# breakout.net
KiCad netlist of a schematic drawn in EAGLE
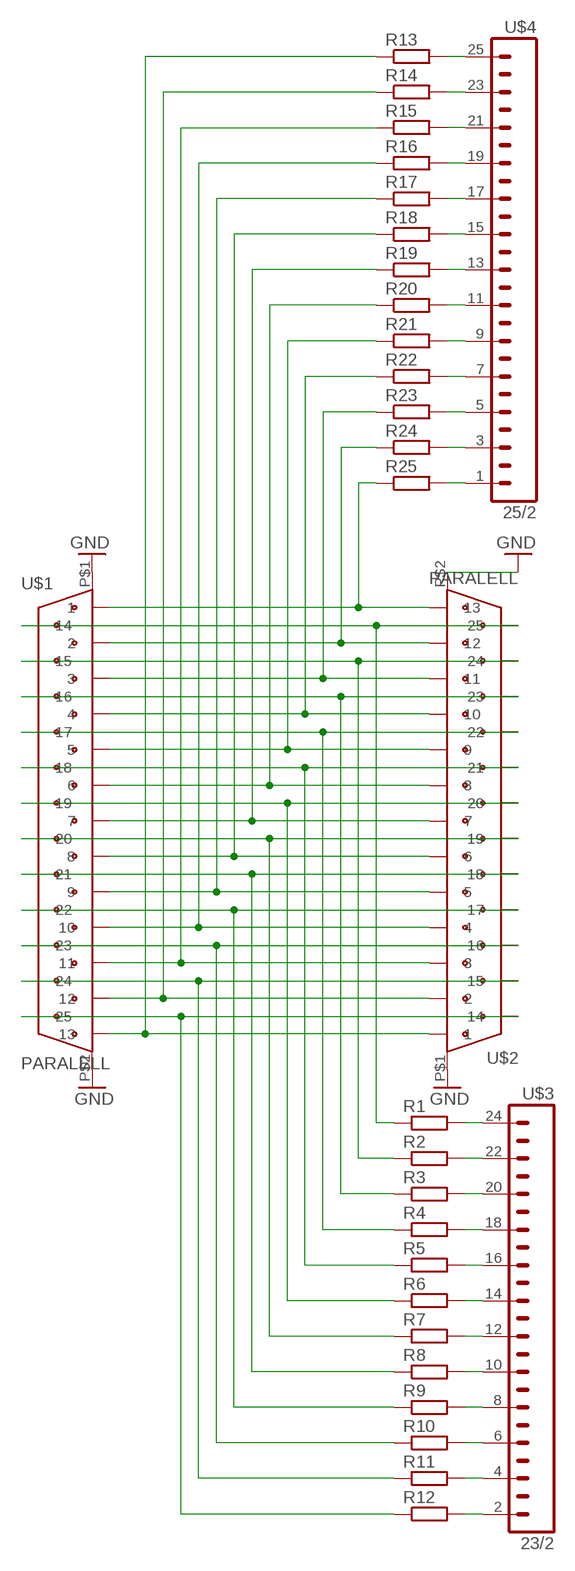
[diagram p0: schematic, sheet 1]

(export (version "E")
  (design (tool "Eeschema 10.0.6"))
  (components
    (comp (ref "R1")
      (value "R-EU_0204/7")
      (footprint "eagle-import:0204_7")
      (libsource (lib "eagle-import") (part "R-EU_0204/7"))
    )
    (comp (ref "R2")
      (value "R-EU_0204/7")
      (footprint "eagle-import:0204_7")
      (libsource (lib "eagle-import") (part "R-EU_0204/7"))
    )
    (comp (ref "R3")
      (value "R-EU_0204/7")
      (footprint "eagle-import:0204_7")
      (libsource (lib "eagle-import") (part "R-EU_0204/7"))
    )
    (comp (ref "R4")
      (value "R-EU_0204/7")
      (footprint "eagle-import:0204_7")
      (libsource (lib "eagle-import") (part "R-EU_0204/7"))
    )
    (comp (ref "R5")
      (value "R-EU_0204/7")
      (footprint "eagle-import:0204_7")
      (libsource (lib "eagle-import") (part "R-EU_0204/7"))
    )
    (comp (ref "R6")
      (value "R-EU_0204/7")
      (footprint "eagle-import:0204_7")
      (libsource (lib "eagle-import") (part "R-EU_0204/7"))
    )
    (comp (ref "R7")
      (value "R-EU_0204/7")
      (footprint "eagle-import:0204_7")
      (libsource (lib "eagle-import") (part "R-EU_0204/7"))
    )
    (comp (ref "R8")
      (value "R-EU_0204/7")
      (footprint "eagle-import:0204_7")
      (libsource (lib "eagle-import") (part "R-EU_0204/7"))
    )
    (comp (ref "R9")
      (value "R-EU_0204/7")
      (footprint "eagle-import:0204_7")
      (libsource (lib "eagle-import") (part "R-EU_0204/7"))
    )
    (comp (ref "R10")
      (value "R-EU_0204/7")
      (footprint "eagle-import:0204_7")
      (libsource (lib "eagle-import") (part "R-EU_0204/7"))
    )
    (comp (ref "R11")
      (value "R-EU_0204/7")
      (footprint "eagle-import:0204_7")
      (libsource (lib "eagle-import") (part "R-EU_0204/7"))
    )
    (comp (ref "R12")
      (value "R-EU_0204/7")
      (footprint "eagle-import:0204_7")
      (libsource (lib "eagle-import") (part "R-EU_0204/7"))
    )
    (comp (ref "R13")
      (value "R-EU_0204/7")
      (footprint "eagle-import:0204_7")
      (libsource (lib "eagle-import") (part "R-EU_0204/7"))
    )
    (comp (ref "R14")
      (value "R-EU_0204/7")
      (footprint "eagle-import:0204_7")
      (libsource (lib "eagle-import") (part "R-EU_0204/7"))
    )
    (comp (ref "R15")
      (value "R-EU_0204/7")
      (footprint "eagle-import:0204_7")
      (libsource (lib "eagle-import") (part "R-EU_0204/7"))
    )
    (comp (ref "R16")
      (value "R-EU_0204/7")
      (footprint "eagle-import:0204_7")
      (libsource (lib "eagle-import") (part "R-EU_0204/7"))
    )
    (comp (ref "R17")
      (value "R-EU_0204/7")
      (footprint "eagle-import:0204_7")
      (libsource (lib "eagle-import") (part "R-EU_0204/7"))
    )
    (comp (ref "R18")
      (value "R-EU_0204/7")
      (footprint "eagle-import:0204_7")
      (libsource (lib "eagle-import") (part "R-EU_0204/7"))
    )
    (comp (ref "R19")
      (value "R-EU_0204/7")
      (footprint "eagle-import:0204_7")
      (libsource (lib "eagle-import") (part "R-EU_0204/7"))
    )
    (comp (ref "R20")
      (value "R-EU_0204/7")
      (footprint "eagle-import:0204_7")
      (libsource (lib "eagle-import") (part "R-EU_0204/7"))
    )
    (comp (ref "R21")
      (value "R-EU_0204/7")
      (footprint "eagle-import:0204_7")
      (libsource (lib "eagle-import") (part "R-EU_0204/7"))
    )
    (comp (ref "R22")
      (value "R-EU_0204/7")
      (footprint "eagle-import:0204_7")
      (libsource (lib "eagle-import") (part "R-EU_0204/7"))
    )
    (comp (ref "R23")
      (value "R-EU_0204/7")
      (footprint "eagle-import:0204_7")
      (libsource (lib "eagle-import") (part "R-EU_0204/7"))
    )
    (comp (ref "R24")
      (value "R-EU_0204/7")
      (footprint "eagle-import:0204_7")
      (libsource (lib "eagle-import") (part "R-EU_0204/7"))
    )
    (comp (ref "R25")
      (value "R-EU_0204/7")
      (footprint "eagle-import:0204_7")
      (libsource (lib "eagle-import") (part "R-EU_0204/7"))
    )
    (comp (ref "U$1")
      (value "PARALELL")
      (footprint "eagle-import:PARALLEL")
      (libsource (lib "eagle-import") (part "PARALELL"))
    )
    (comp (ref "U$2")
      (value "PARALELL")
      (footprint "eagle-import:PARALLEL")
      (libsource (lib "eagle-import") (part "PARALELL"))
    )
    (comp (ref "U$3")
      (value "23/2")
      (footprint "eagle-import:1X23")
      (libsource (lib "eagle-import") (part "23/2"))
    )
    (comp (ref "U$4")
      (value "25/2")
      (footprint "eagle-import:1X25")
      (libsource (lib "eagle-import") (part "25/2"))
    )
  )
  (nets
    (net (code "1") (name "GND") (class "Default")
      (node (ref "U$1") (pin "P$1") (pinfunction "P$26_P$1") (pintype "bidirectional"))
      (node (ref "U$1") (pin "P$2") (pinfunction "P$27_P$2") (pintype "bidirectional"))
      (node (ref "U$2") (pin "P$1") (pinfunction "P$26_P$1") (pintype "bidirectional"))
      (node (ref "U$2") (pin "P$2") (pinfunction "P$27_P$2") (pintype "bidirectional"))
    )
    (net (code "2") (name "Net-(R1-Pad2)") (class "Default")
      (node (ref "R1") (pin "2") (pinfunction "2_2") (pintype "passive"))
      (node (ref "U$3") (pin "24") (pinfunction "24_24") (pintype "passive"))
    )
    (net (code "3") (name "Net-(R2-Pad2)") (class "Default")
      (node (ref "R2") (pin "2") (pinfunction "2_2") (pintype "passive"))
      (node (ref "U$3") (pin "22") (pinfunction "22_22") (pintype "passive"))
    )
    (net (code "4") (name "Net-(R3-Pad2)") (class "Default")
      (node (ref "R3") (pin "2") (pinfunction "2_2") (pintype "passive"))
      (node (ref "U$3") (pin "20") (pinfunction "20_20") (pintype "passive"))
    )
    (net (code "5") (name "Net-(R4-Pad2)") (class "Default")
      (node (ref "R4") (pin "2") (pinfunction "2_2") (pintype "passive"))
      (node (ref "U$3") (pin "18") (pinfunction "18_18") (pintype "passive"))
    )
    (net (code "6") (name "Net-(R5-Pad2)") (class "Default")
      (node (ref "R5") (pin "2") (pinfunction "2_2") (pintype "passive"))
      (node (ref "U$3") (pin "16") (pinfunction "16_16") (pintype "passive"))
    )
    (net (code "7") (name "Net-(R6-Pad2)") (class "Default")
      (node (ref "R6") (pin "2") (pinfunction "2_2") (pintype "passive"))
      (node (ref "U$3") (pin "14") (pinfunction "14_14") (pintype "passive"))
    )
    (net (code "8") (name "Net-(R7-Pad2)") (class "Default")
      (node (ref "R7") (pin "2") (pinfunction "2_2") (pintype "passive"))
      (node (ref "U$3") (pin "12") (pinfunction "12_12") (pintype "passive"))
    )
    (net (code "9") (name "Net-(R8-Pad2)") (class "Default")
      (node (ref "R8") (pin "2") (pinfunction "2_2") (pintype "passive"))
      (node (ref "U$3") (pin "10") (pinfunction "10_10") (pintype "passive"))
    )
    (net (code "10") (name "Net-(R9-Pad2)") (class "Default")
      (node (ref "R9") (pin "2") (pinfunction "2_2") (pintype "passive"))
      (node (ref "U$3") (pin "8") (pinfunction "8_8") (pintype "passive"))
    )
    (net (code "11") (name "Net-(R10-Pad2)") (class "Default")
      (node (ref "R10") (pin "2") (pinfunction "2_2") (pintype "passive"))
      (node (ref "U$3") (pin "6") (pinfunction "6_6") (pintype "passive"))
    )
    (net (code "12") (name "Net-(R11-Pad2)") (class "Default")
      (node (ref "R11") (pin "2") (pinfunction "2_2") (pintype "passive"))
      (node (ref "U$3") (pin "4") (pinfunction "4_4") (pintype "passive"))
    )
    (net (code "13") (name "Net-(R12-Pad2)") (class "Default")
      (node (ref "R12") (pin "2") (pinfunction "2_2") (pintype "passive"))
      (node (ref "U$3") (pin "2") (pinfunction "2_2") (pintype "passive"))
    )
    (net (code "14") (name "Net-(R13-Pad2)") (class "Default")
      (node (ref "R13") (pin "2") (pinfunction "2_2") (pintype "passive"))
      (node (ref "U$4") (pin "25") (pinfunction "25_25") (pintype "passive"))
    )
    (net (code "15") (name "Net-(R14-Pad2)") (class "Default")
      (node (ref "R14") (pin "2") (pinfunction "2_2") (pintype "passive"))
      (node (ref "U$4") (pin "23") (pinfunction "23_23") (pintype "passive"))
    )
    (net (code "16") (name "Net-(R15-Pad2)") (class "Default")
      (node (ref "R15") (pin "2") (pinfunction "2_2") (pintype "passive"))
      (node (ref "U$4") (pin "21") (pinfunction "21_21") (pintype "passive"))
    )
    (net (code "17") (name "Net-(R16-Pad2)") (class "Default")
      (node (ref "R16") (pin "2") (pinfunction "2_2") (pintype "passive"))
      (node (ref "U$4") (pin "19") (pinfunction "19_19") (pintype "passive"))
    )
    (net (code "18") (name "Net-(R17-Pad2)") (class "Default")
      (node (ref "R17") (pin "2") (pinfunction "2_2") (pintype "passive"))
      (node (ref "U$4") (pin "17") (pinfunction "17_17") (pintype "passive"))
    )
    (net (code "19") (name "Net-(R18-Pad2)") (class "Default")
      (node (ref "R18") (pin "2") (pinfunction "2_2") (pintype "passive"))
      (node (ref "U$4") (pin "15") (pinfunction "15_15") (pintype "passive"))
    )
    (net (code "20") (name "Net-(R19-Pad2)") (class "Default")
      (node (ref "R19") (pin "2") (pinfunction "2_2") (pintype "passive"))
      (node (ref "U$4") (pin "13") (pinfunction "13_13") (pintype "passive"))
    )
    (net (code "21") (name "Net-(R20-Pad2)") (class "Default")
      (node (ref "R20") (pin "2") (pinfunction "2_2") (pintype "passive"))
      (node (ref "U$4") (pin "11") (pinfunction "11_11") (pintype "passive"))
    )
    (net (code "22") (name "Net-(R21-Pad2)") (class "Default")
      (node (ref "R21") (pin "2") (pinfunction "2_2") (pintype "passive"))
      (node (ref "U$4") (pin "9") (pinfunction "9_9") (pintype "passive"))
    )
    (net (code "23") (name "Net-(R22-Pad2)") (class "Default")
      (node (ref "R22") (pin "2") (pinfunction "2_2") (pintype "passive"))
      (node (ref "U$4") (pin "7") (pinfunction "7_7") (pintype "passive"))
    )
    (net (code "24") (name "Net-(R23-Pad2)") (class "Default")
      (node (ref "R23") (pin "2") (pinfunction "2_2") (pintype "passive"))
      (node (ref "U$4") (pin "5") (pinfunction "5_5") (pintype "passive"))
    )
    (net (code "25") (name "Net-(R24-Pad2)") (class "Default")
      (node (ref "R24") (pin "2") (pinfunction "2_2") (pintype "passive"))
      (node (ref "U$4") (pin "3") (pinfunction "3_3") (pintype "passive"))
    )
    (net (code "26") (name "Net-(R25-Pad2)") (class "Default")
      (node (ref "R25") (pin "2") (pinfunction "2_2") (pintype "passive"))
      (node (ref "U$4") (pin "1") (pinfunction "1_1") (pintype "passive"))
    )
    (net (code "27") (name "Net-(U$1-1)") (class "Default")
      (node (ref "R25") (pin "1") (pinfunction "1_1") (pintype "passive"))
      (node (ref "U$1") (pin "P$3") (pinfunction "1_P$3") (pintype "bidirectional"))
      (node (ref "U$2") (pin "P$15") (pinfunction "13_P$15") (pintype "bidirectional"))
    )
    (net (code "28") (name "Net-(U$1-2)") (class "Default")
      (node (ref "R24") (pin "1") (pinfunction "1_1") (pintype "passive"))
      (node (ref "U$1") (pin "P$4") (pinfunction "2_P$4") (pintype "bidirectional"))
      (node (ref "U$2") (pin "P$14") (pinfunction "12_P$14") (pintype "bidirectional"))
    )
    (net (code "29") (name "Net-(U$1-3)") (class "Default")
      (node (ref "R23") (pin "1") (pinfunction "1_1") (pintype "passive"))
      (node (ref "U$1") (pin "P$5") (pinfunction "3_P$5") (pintype "bidirectional"))
      (node (ref "U$2") (pin "P$13") (pinfunction "11_P$13") (pintype "bidirectional"))
    )
    (net (code "30") (name "Net-(U$1-4)") (class "Default")
      (node (ref "R22") (pin "1") (pinfunction "1_1") (pintype "passive"))
      (node (ref "U$1") (pin "P$6") (pinfunction "4_P$6") (pintype "bidirectional"))
      (node (ref "U$2") (pin "P$12") (pinfunction "10_P$12") (pintype "bidirectional"))
    )
    (net (code "31") (name "Net-(U$1-5)") (class "Default")
      (node (ref "R21") (pin "1") (pinfunction "1_1") (pintype "passive"))
      (node (ref "U$1") (pin "P$7") (pinfunction "5_P$7") (pintype "bidirectional"))
      (node (ref "U$2") (pin "P$11") (pinfunction "9_P$11") (pintype "bidirectional"))
    )
    (net (code "32") (name "Net-(U$1-6)") (class "Default")
      (node (ref "R20") (pin "1") (pinfunction "1_1") (pintype "passive"))
      (node (ref "U$1") (pin "P$8") (pinfunction "6_P$8") (pintype "bidirectional"))
      (node (ref "U$2") (pin "P$10") (pinfunction "8_P$10") (pintype "bidirectional"))
    )
    (net (code "33") (name "Net-(U$1-7)") (class "Default")
      (node (ref "R19") (pin "1") (pinfunction "1_1") (pintype "passive"))
      (node (ref "U$1") (pin "P$9") (pinfunction "7_P$9") (pintype "bidirectional"))
      (node (ref "U$2") (pin "P$9") (pinfunction "7_P$9") (pintype "bidirectional"))
    )
    (net (code "34") (name "Net-(U$1-8)") (class "Default")
      (node (ref "R18") (pin "1") (pinfunction "1_1") (pintype "passive"))
      (node (ref "U$1") (pin "P$10") (pinfunction "8_P$10") (pintype "bidirectional"))
      (node (ref "U$2") (pin "P$8") (pinfunction "6_P$8") (pintype "bidirectional"))
    )
    (net (code "35") (name "Net-(U$1-9)") (class "Default")
      (node (ref "R17") (pin "1") (pinfunction "1_1") (pintype "passive"))
      (node (ref "U$1") (pin "P$11") (pinfunction "9_P$11") (pintype "bidirectional"))
      (node (ref "U$2") (pin "P$7") (pinfunction "5_P$7") (pintype "bidirectional"))
    )
    (net (code "36") (name "Net-(U$1-10)") (class "Default")
      (node (ref "R16") (pin "1") (pinfunction "1_1") (pintype "passive"))
      (node (ref "U$1") (pin "P$12") (pinfunction "10_P$12") (pintype "bidirectional"))
      (node (ref "U$2") (pin "P$6") (pinfunction "4_P$6") (pintype "bidirectional"))
    )
    (net (code "37") (name "Net-(U$1-11)") (class "Default")
      (node (ref "R15") (pin "1") (pinfunction "1_1") (pintype "passive"))
      (node (ref "U$1") (pin "P$13") (pinfunction "11_P$13") (pintype "bidirectional"))
      (node (ref "U$2") (pin "P$5") (pinfunction "3_P$5") (pintype "bidirectional"))
    )
    (net (code "38") (name "Net-(U$1-12)") (class "Default")
      (node (ref "R14") (pin "1") (pinfunction "1_1") (pintype "passive"))
      (node (ref "U$1") (pin "P$14") (pinfunction "12_P$14") (pintype "bidirectional"))
      (node (ref "U$2") (pin "P$4") (pinfunction "2_P$4") (pintype "bidirectional"))
    )
    (net (code "39") (name "Net-(U$1-13)") (class "Default")
      (node (ref "R13") (pin "1") (pinfunction "1_1") (pintype "passive"))
      (node (ref "U$1") (pin "P$15") (pinfunction "13_P$15") (pintype "bidirectional"))
      (node (ref "U$2") (pin "P$3") (pinfunction "1_P$3") (pintype "bidirectional"))
    )
    (net (code "40") (name "Net-(U$1-14)") (class "Default")
      (node (ref "R1") (pin "1") (pinfunction "1_1") (pintype "passive"))
      (node (ref "U$1") (pin "P$16") (pinfunction "14_P$16") (pintype "bidirectional"))
      (node (ref "U$2") (pin "P$27") (pinfunction "25_P$27") (pintype "bidirectional"))
    )
    (net (code "41") (name "Net-(U$1-15)") (class "Default")
      (node (ref "R2") (pin "1") (pinfunction "1_1") (pintype "passive"))
      (node (ref "U$1") (pin "P$17") (pinfunction "15_P$17") (pintype "bidirectional"))
      (node (ref "U$2") (pin "P$26") (pinfunction "24_P$26") (pintype "bidirectional"))
    )
    (net (code "42") (name "Net-(U$1-16)") (class "Default")
      (node (ref "R3") (pin "1") (pinfunction "1_1") (pintype "passive"))
      (node (ref "U$1") (pin "P$18") (pinfunction "16_P$18") (pintype "bidirectional"))
      (node (ref "U$2") (pin "P$25") (pinfunction "23_P$25") (pintype "bidirectional"))
    )
    (net (code "43") (name "Net-(U$1-17)") (class "Default")
      (node (ref "R4") (pin "1") (pinfunction "1_1") (pintype "passive"))
      (node (ref "U$1") (pin "P$19") (pinfunction "17_P$19") (pintype "bidirectional"))
      (node (ref "U$2") (pin "P$24") (pinfunction "22_P$24") (pintype "bidirectional"))
    )
    (net (code "44") (name "Net-(U$1-18)") (class "Default")
      (node (ref "R5") (pin "1") (pinfunction "1_1") (pintype "passive"))
      (node (ref "U$1") (pin "P$20") (pinfunction "18_P$20") (pintype "bidirectional"))
      (node (ref "U$2") (pin "P$23") (pinfunction "21_P$23") (pintype "bidirectional"))
    )
    (net (code "45") (name "Net-(U$1-19)") (class "Default")
      (node (ref "R6") (pin "1") (pinfunction "1_1") (pintype "passive"))
      (node (ref "U$1") (pin "P$21") (pinfunction "19_P$21") (pintype "bidirectional"))
      (node (ref "U$2") (pin "P$22") (pinfunction "20_P$22") (pintype "bidirectional"))
    )
    (net (code "46") (name "Net-(U$1-20)") (class "Default")
      (node (ref "R7") (pin "1") (pinfunction "1_1") (pintype "passive"))
      (node (ref "U$1") (pin "P$22") (pinfunction "20_P$22") (pintype "bidirectional"))
      (node (ref "U$2") (pin "P$21") (pinfunction "19_P$21") (pintype "bidirectional"))
    )
    (net (code "47") (name "Net-(U$1-21)") (class "Default")
      (node (ref "R8") (pin "1") (pinfunction "1_1") (pintype "passive"))
      (node (ref "U$1") (pin "P$23") (pinfunction "21_P$23") (pintype "bidirectional"))
      (node (ref "U$2") (pin "P$20") (pinfunction "18_P$20") (pintype "bidirectional"))
    )
    (net (code "48") (name "Net-(U$1-22)") (class "Default")
      (node (ref "R9") (pin "1") (pinfunction "1_1") (pintype "passive"))
      (node (ref "U$1") (pin "P$24") (pinfunction "22_P$24") (pintype "bidirectional"))
      (node (ref "U$2") (pin "P$19") (pinfunction "17_P$19") (pintype "bidirectional"))
    )
    (net (code "49") (name "Net-(U$1-23)") (class "Default")
      (node (ref "R10") (pin "1") (pinfunction "1_1") (pintype "passive"))
      (node (ref "U$1") (pin "P$25") (pinfunction "23_P$25") (pintype "bidirectional"))
      (node (ref "U$2") (pin "P$18") (pinfunction "16_P$18") (pintype "bidirectional"))
    )
    (net (code "50") (name "Net-(U$1-24)") (class "Default")
      (node (ref "R11") (pin "1") (pinfunction "1_1") (pintype "passive"))
      (node (ref "U$1") (pin "P$26") (pinfunction "24_P$26") (pintype "bidirectional"))
      (node (ref "U$2") (pin "P$17") (pinfunction "15_P$17") (pintype "bidirectional"))
    )
    (net (code "51") (name "Net-(U$1-25)") (class "Default")
      (node (ref "R12") (pin "1") (pinfunction "1_1") (pintype "passive"))
      (node (ref "U$1") (pin "P$27") (pinfunction "25_P$27") (pintype "bidirectional"))
      (node (ref "U$2") (pin "P$16") (pinfunction "14_P$16") (pintype "bidirectional"))
    )
  )
)
